# BiPAP_PCB_V2_Released.net
KiCad netlist of a schematic drawn in EAGLE
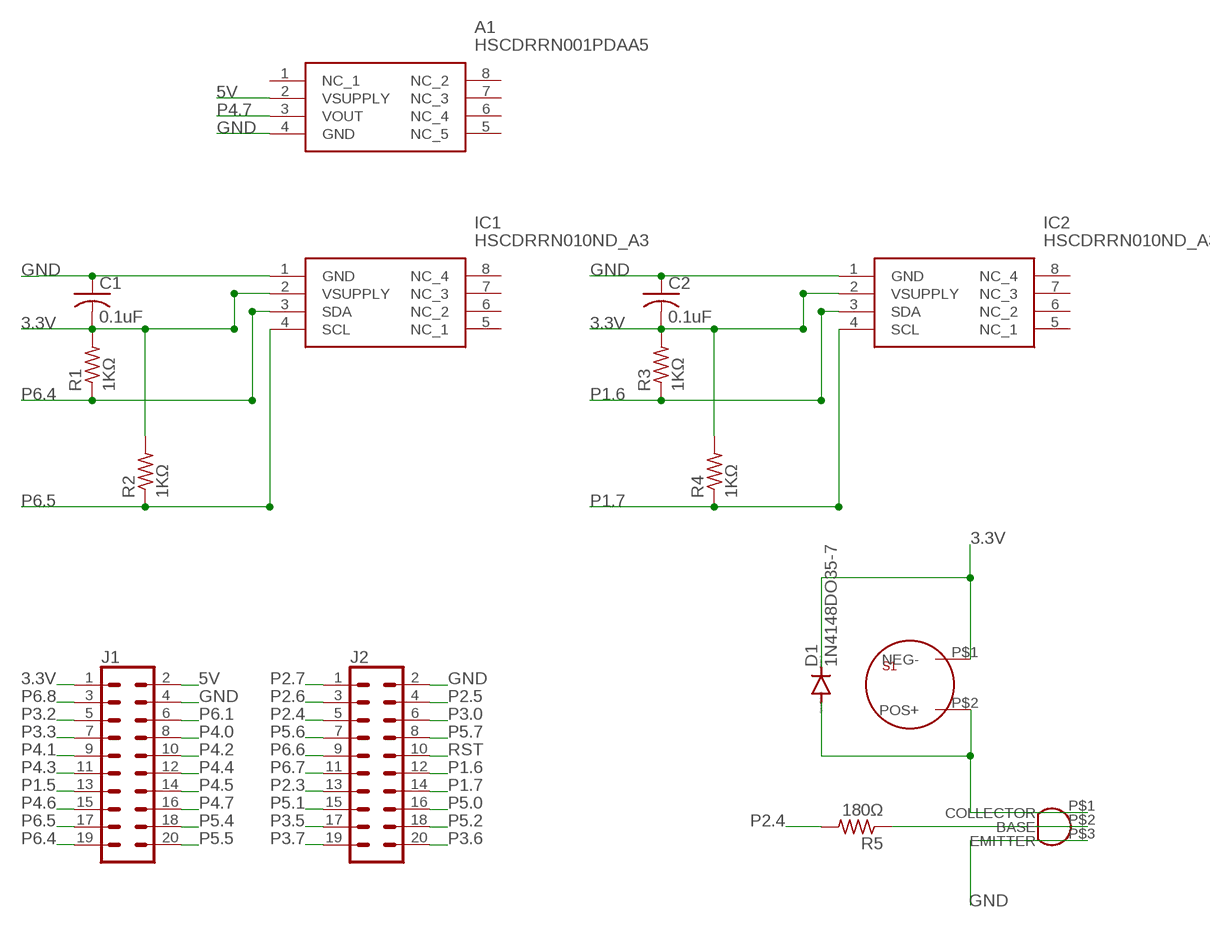
[diagram p0: schematic, sheet 1]

(export (version "E")
  (design (tool "Eeschema 10.0.6"))
  (components
    (comp (ref "A1")
      (value "HSCDRRN001PDAA5")
      (footprint "eagle-import:HSCDRRN001PDAA5")
      (libsource (lib "eagle-import") (part "HSCDRRN001PDAA5"))
    )
    (comp (ref "C1")
      (value "0.1uF")
      (footprint "eagle-import:C0805")
      (libsource (lib "eagle-import") (part "C-USC0805"))
    )
    (comp (ref "C2")
      (value "0.1uF")
      (footprint "eagle-import:C0805")
      (libsource (lib "eagle-import") (part "C-USC0805"))
    )
    (comp (ref "D1")
      (value "1N4148DO35-7")
      (footprint "eagle-import:DO35-7")
      (libsource (lib "eagle-import") (part "1N4148DO35-7"))
    )
    (comp (ref "IC1")
      (value "HSCDRRN010ND_A3")
      (footprint "eagle-import:HSCDRRN010ND2A3")
      (fields
        (field (name "MANUFACTURER_PART_NUMBER") "HSCDRRN010ND2A3")
        (field (name "MOUSER_PART_NUMBER") "785-HSCDRRN010ND2A3")
      )
      (libsource (lib "eagle-import") (part "HSCDRRN010ND2A3"))
    )
    (comp (ref "IC2")
      (value "HSCDRRN010ND_A3")
      (footprint "eagle-import:HSCDRRN010ND2A3")
      (fields
        (field (name "MANUFACTURER_PART_NUMBER") "HSCDRRN010ND2A3")
        (field (name "MOUSER_PART_NUMBER") "785-HSCDRRN010ND2A3")
      )
      (libsource (lib "eagle-import") (part "HSCDRRN010ND2A3"))
    )
    (comp (ref "J1")
      (value "CONN_10X2")
      (footprint "eagle-import:2X10")
      (libsource (lib "eagle-import") (part "CONN_10X2"))
    )
    (comp (ref "J2")
      (value "CONN_10X2")
      (footprint "eagle-import:2X10")
      (libsource (lib "eagle-import") (part "CONN_10X2"))
    )
    (comp (ref "R1")
      (value "1KΩ")
      (footprint "eagle-import:R0805")
      (libsource (lib "eagle-import") (part "R-US_R0805"))
    )
    (comp (ref "R2")
      (value "1KΩ")
      (footprint "eagle-import:R0805")
      (libsource (lib "eagle-import") (part "R-US_R0805"))
    )
    (comp (ref "R3")
      (value "1KΩ")
      (footprint "eagle-import:R0805")
      (libsource (lib "eagle-import") (part "R-US_R0805"))
    )
    (comp (ref "R4")
      (value "1KΩ")
      (footprint "eagle-import:R0805")
      (libsource (lib "eagle-import") (part "R-US_R0805"))
    )
    (comp (ref "R5")
      (value "180Ω")
      (footprint "eagle-import:R0805")
      (libsource (lib "eagle-import") (part "R-US_R0805"))
    )
    (comp (ref "S1")
      (value "CEET120B085")
      (footprint "eagle-import:CEET120B085")
      (libsource (lib "eagle-import") (part "CEET120B085"))
    )
    (comp (ref "T1")
      (value "BC337")
      (footprint "eagle-import:BC337")
      (libsource (lib "eagle-import") (part "BC337"))
    )
  )
  (nets
    (net (code "1") (name "/3.3V") (class "Default")
      (node (ref "C1") (pin "2") (pinfunction "2_2") (pintype "passive"))
      (node (ref "C2") (pin "2") (pinfunction "2_2") (pintype "passive"))
      (node (ref "D1") (pin "C") (pinfunction "C_C") (pintype "passive"))
      (node (ref "IC1") (pin "2") (pinfunction "VSUPPLY_2") (pintype "bidirectional"))
      (node (ref "IC2") (pin "2") (pinfunction "VSUPPLY_2") (pintype "bidirectional"))
      (node (ref "J1") (pin "1") (pinfunction "1_1") (pintype "passive"))
      (node (ref "R1") (pin "2") (pinfunction "2_2") (pintype "passive"))
      (node (ref "R2") (pin "2") (pinfunction "2_2") (pintype "passive"))
      (node (ref "R3") (pin "2") (pinfunction "2_2") (pintype "passive"))
      (node (ref "R4") (pin "2") (pinfunction "2_2") (pintype "passive"))
      (node (ref "S1") (pin "P$1") (pinfunction "NEG-_P$1") (pintype "bidirectional"))
    )
    (net (code "2") (name "/5V") (class "Default")
      (node (ref "A1") (pin "2") (pinfunction "VSUPPLY_2") (pintype "bidirectional"))
      (node (ref "J1") (pin "2") (pinfunction "2_2") (pintype "passive"))
    )
    (net (code "3") (name "/GND") (class "Default")
      (node (ref "A1") (pin "4") (pinfunction "GND_4") (pintype "bidirectional"))
      (node (ref "C1") (pin "1") (pinfunction "1_1") (pintype "passive"))
      (node (ref "C2") (pin "1") (pinfunction "1_1") (pintype "passive"))
      (node (ref "IC1") (pin "1") (pinfunction "GND_1") (pintype "bidirectional"))
      (node (ref "IC2") (pin "1") (pinfunction "GND_1") (pintype "bidirectional"))
      (node (ref "J1") (pin "4") (pinfunction "4_4") (pintype "passive"))
      (node (ref "J2") (pin "2") (pinfunction "2_2") (pintype "passive"))
      (node (ref "T1") (pin "P$3") (pinfunction "EMITTER_P$3") (pintype "bidirectional"))
    )
    (net (code "4") (name "/P1.5") (class "Default")
      (node (ref "J1") (pin "13") (pinfunction "13_13") (pintype "passive"))
    )
    (net (code "5") (name "/P1.6") (class "Default")
      (node (ref "IC2") (pin "3") (pinfunction "SDA_3") (pintype "bidirectional"))
      (node (ref "J2") (pin "12") (pinfunction "12_12") (pintype "passive"))
      (node (ref "R3") (pin "1") (pinfunction "1_1") (pintype "passive"))
    )
    (net (code "6") (name "/P1.7") (class "Default")
      (node (ref "IC2") (pin "4") (pinfunction "SCL_4") (pintype "bidirectional"))
      (node (ref "J2") (pin "14") (pinfunction "14_14") (pintype "passive"))
      (node (ref "R4") (pin "1") (pinfunction "1_1") (pintype "passive"))
    )
    (net (code "7") (name "/P2.3") (class "Default")
      (node (ref "J2") (pin "13") (pinfunction "13_13") (pintype "passive"))
    )
    (net (code "8") (name "/P2.4") (class "Default")
      (node (ref "J2") (pin "5") (pinfunction "5_5") (pintype "passive"))
      (node (ref "R5") (pin "2") (pinfunction "2_2") (pintype "passive"))
    )
    (net (code "9") (name "/P2.5") (class "Default")
      (node (ref "J2") (pin "4") (pinfunction "4_4") (pintype "passive"))
    )
    (net (code "10") (name "/P2.6") (class "Default")
      (node (ref "J2") (pin "3") (pinfunction "3_3") (pintype "passive"))
    )
    (net (code "11") (name "/P2.7") (class "Default")
      (node (ref "J2") (pin "1") (pinfunction "1_1") (pintype "passive"))
    )
    (net (code "12") (name "/P3.0") (class "Default")
      (node (ref "J2") (pin "6") (pinfunction "6_6") (pintype "passive"))
    )
    (net (code "13") (name "/P3.2") (class "Default")
      (node (ref "J1") (pin "5") (pinfunction "5_5") (pintype "passive"))
    )
    (net (code "14") (name "/P3.3") (class "Default")
      (node (ref "J1") (pin "7") (pinfunction "7_7") (pintype "passive"))
    )
    (net (code "15") (name "/P3.5") (class "Default")
      (node (ref "J2") (pin "17") (pinfunction "17_17") (pintype "passive"))
    )
    (net (code "16") (name "/P3.6") (class "Default")
      (node (ref "J2") (pin "20") (pinfunction "20_20") (pintype "passive"))
    )
    (net (code "17") (name "/P3.7") (class "Default")
      (node (ref "J2") (pin "19") (pinfunction "19_19") (pintype "passive"))
    )
    (net (code "18") (name "/P4.0") (class "Default")
      (node (ref "J1") (pin "8") (pinfunction "8_8") (pintype "passive"))
    )
    (net (code "19") (name "/P4.1") (class "Default")
      (node (ref "J1") (pin "9") (pinfunction "9_9") (pintype "passive"))
    )
    (net (code "20") (name "/P4.2") (class "Default")
      (node (ref "J1") (pin "10") (pinfunction "10_10") (pintype "passive"))
    )
    (net (code "21") (name "/P4.3") (class "Default")
      (node (ref "J1") (pin "11") (pinfunction "11_11") (pintype "passive"))
    )
    (net (code "22") (name "/P4.4") (class "Default")
      (node (ref "J1") (pin "12") (pinfunction "12_12") (pintype "passive"))
    )
    (net (code "23") (name "/P4.5") (class "Default")
      (node (ref "J1") (pin "14") (pinfunction "14_14") (pintype "passive"))
    )
    (net (code "24") (name "/P4.6") (class "Default")
      (node (ref "J1") (pin "15") (pinfunction "15_15") (pintype "passive"))
    )
    (net (code "25") (name "/P4.7") (class "Default")
      (node (ref "A1") (pin "3") (pinfunction "VOUT_3") (pintype "bidirectional"))
      (node (ref "J1") (pin "16") (pinfunction "16_16") (pintype "passive"))
    )
    (net (code "26") (name "/P5.0") (class "Default")
      (node (ref "J2") (pin "16") (pinfunction "16_16") (pintype "passive"))
    )
    (net (code "27") (name "/P5.1") (class "Default")
      (node (ref "J2") (pin "15") (pinfunction "15_15") (pintype "passive"))
    )
    (net (code "28") (name "/P5.2") (class "Default")
      (node (ref "J2") (pin "18") (pinfunction "18_18") (pintype "passive"))
    )
    (net (code "29") (name "/P5.4") (class "Default")
      (node (ref "J1") (pin "18") (pinfunction "18_18") (pintype "passive"))
    )
    (net (code "30") (name "/P5.5") (class "Default")
      (node (ref "J1") (pin "20") (pinfunction "20_20") (pintype "passive"))
    )
    (net (code "31") (name "/P5.6") (class "Default")
      (node (ref "J2") (pin "7") (pinfunction "7_7") (pintype "passive"))
    )
    (net (code "32") (name "/P5.7") (class "Default")
      (node (ref "J2") (pin "8") (pinfunction "8_8") (pintype "passive"))
    )
    (net (code "33") (name "/P6.1") (class "Default")
      (node (ref "J1") (pin "6") (pinfunction "6_6") (pintype "passive"))
    )
    (net (code "34") (name "/P6.4") (class "Default")
      (node (ref "IC1") (pin "3") (pinfunction "SDA_3") (pintype "bidirectional"))
      (node (ref "J1") (pin "19") (pinfunction "19_19") (pintype "passive"))
      (node (ref "R1") (pin "1") (pinfunction "1_1") (pintype "passive"))
    )
    (net (code "35") (name "/P6.5") (class "Default")
      (node (ref "IC1") (pin "4") (pinfunction "SCL_4") (pintype "bidirectional"))
      (node (ref "J1") (pin "17") (pinfunction "17_17") (pintype "passive"))
      (node (ref "R2") (pin "1") (pinfunction "1_1") (pintype "passive"))
    )
    (net (code "36") (name "/P6.6") (class "Default")
      (node (ref "J2") (pin "9") (pinfunction "9_9") (pintype "passive"))
    )
    (net (code "37") (name "/P6.7") (class "Default")
      (node (ref "J2") (pin "11") (pinfunction "11_11") (pintype "passive"))
    )
    (net (code "38") (name "/P6.8") (class "Default")
      (node (ref "J1") (pin "3") (pinfunction "3_3") (pintype "passive"))
    )
    (net (code "39") (name "/RST") (class "Default")
      (node (ref "J2") (pin "10") (pinfunction "10_10") (pintype "passive"))
    )
    (net (code "40") (name "Net-(S1-POS+)") (class "Default")
      (node (ref "D1") (pin "A") (pinfunction "A_A") (pintype "passive"))
      (node (ref "S1") (pin "P$2") (pinfunction "POS+_P$2") (pintype "bidirectional"))
      (node (ref "T1") (pin "P$1") (pinfunction "COLLECTOR_P$1") (pintype "bidirectional"))
    )
    (net (code "41") (name "Net-(T1-BASE)") (class "Default")
      (node (ref "R5") (pin "1") (pinfunction "1_1") (pintype "passive"))
      (node (ref "T1") (pin "P$2") (pinfunction "BASE_P$2") (pintype "bidirectional"))
    )
    (net (code "42") (name "unconnected-(A1-NC_1-Pad1)") (class "Default")
      (node (ref "A1") (pin "1") (pinfunction "NC_1_1") (pintype "bidirectional"))
    )
    (net (code "43") (name "unconnected-(A1-NC_2-Pad8)") (class "Default")
      (node (ref "A1") (pin "8") (pinfunction "NC_2_8") (pintype "bidirectional"))
    )
    (net (code "44") (name "unconnected-(A1-NC_3-Pad7)") (class "Default")
      (node (ref "A1") (pin "7") (pinfunction "NC_3_7") (pintype "bidirectional"))
    )
    (net (code "45") (name "unconnected-(A1-NC_4-Pad6)") (class "Default")
      (node (ref "A1") (pin "6") (pinfunction "NC_4_6") (pintype "bidirectional"))
    )
    (net (code "46") (name "unconnected-(A1-NC_5-Pad5)") (class "Default")
      (node (ref "A1") (pin "5") (pinfunction "NC_5_5") (pintype "bidirectional"))
    )
    (net (code "47") (name "unconnected-(IC1-NC_1-Pad5)") (class "Default")
      (node (ref "IC1") (pin "5") (pinfunction "NC_1_5") (pintype "bidirectional"))
    )
    (net (code "48") (name "unconnected-(IC1-NC_2-Pad6)") (class "Default")
      (node (ref "IC1") (pin "6") (pinfunction "NC_2_6") (pintype "bidirectional"))
    )
    (net (code "49") (name "unconnected-(IC1-NC_3-Pad7)") (class "Default")
      (node (ref "IC1") (pin "7") (pinfunction "NC_3_7") (pintype "bidirectional"))
    )
    (net (code "50") (name "unconnected-(IC1-NC_4-Pad8)") (class "Default")
      (node (ref "IC1") (pin "8") (pinfunction "NC_4_8") (pintype "bidirectional"))
    )
    (net (code "51") (name "unconnected-(IC2-NC_1-Pad5)") (class "Default")
      (node (ref "IC2") (pin "5") (pinfunction "NC_1_5") (pintype "bidirectional"))
    )
    (net (code "52") (name "unconnected-(IC2-NC_2-Pad6)") (class "Default")
      (node (ref "IC2") (pin "6") (pinfunction "NC_2_6") (pintype "bidirectional"))
    )
    (net (code "53") (name "unconnected-(IC2-NC_3-Pad7)") (class "Default")
      (node (ref "IC2") (pin "7") (pinfunction "NC_3_7") (pintype "bidirectional"))
    )
    (net (code "54") (name "unconnected-(IC2-NC_4-Pad8)") (class "Default")
      (node (ref "IC2") (pin "8") (pinfunction "NC_4_8") (pintype "bidirectional"))
    )
  )
)
